# floppycontrol_mcu.net
KiCad netlist of a schematic drawn in EAGLE
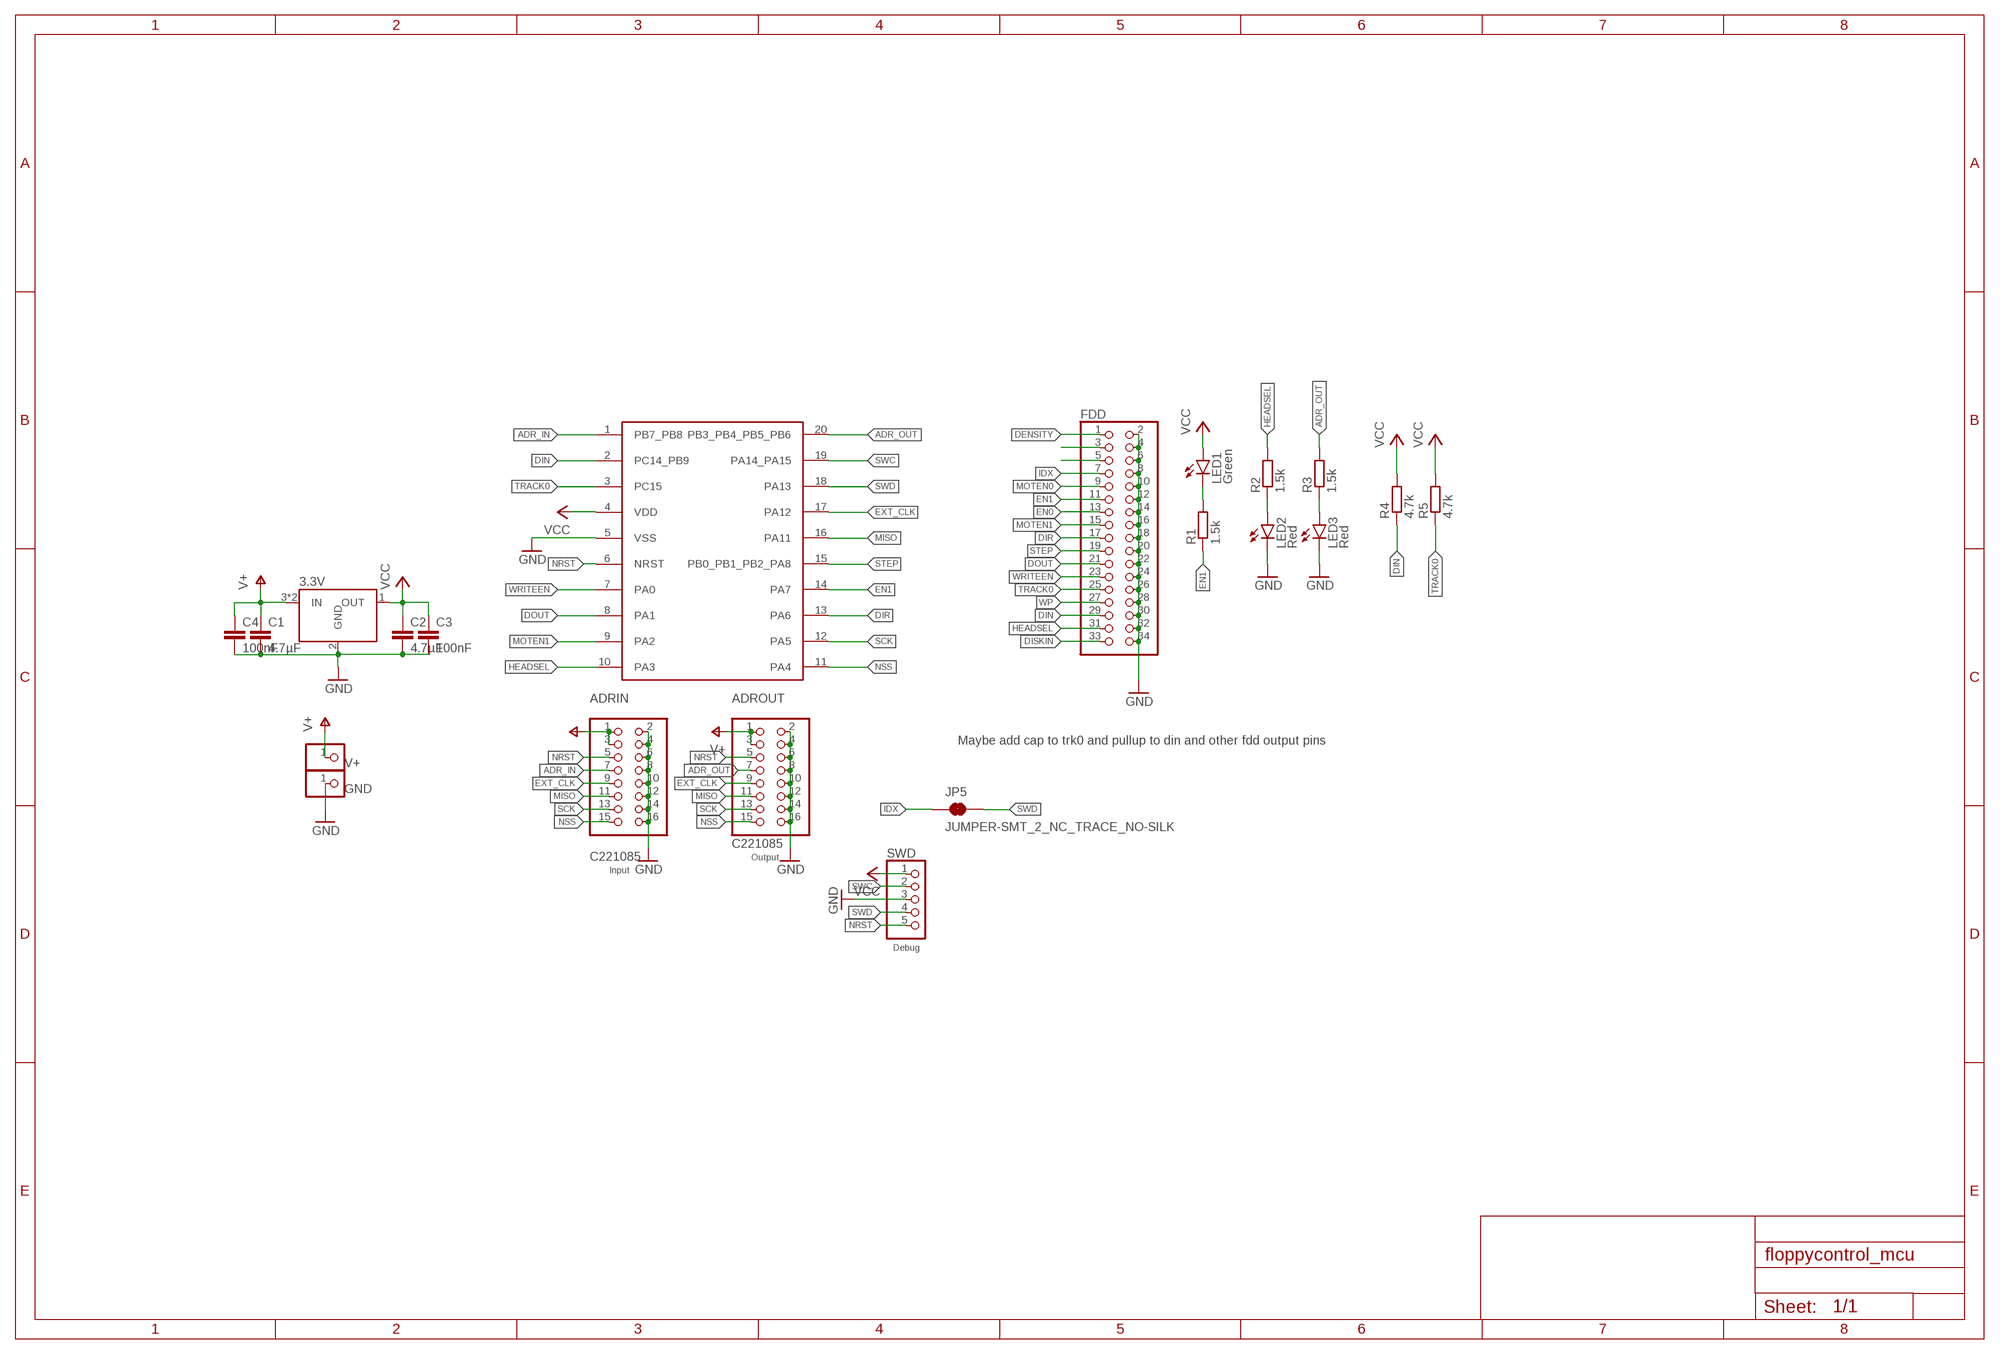
[diagram p0: schematic, sheet 1]

(export (version "E")
  (design (tool "Eeschema 10.0.6"))
  (components
    (comp (ref "ADRIN")
      (value "C221085")
      (footprint "eagle-import:2X08_90")
      (libsource (lib "eagle-import") (part "PINHD-2X8/90"))
    )
    (comp (ref "ADROUT")
      (value "C221085")
      (footprint "eagle-import:2X08_90")
      (libsource (lib "eagle-import") (part "PINHD-2X8/90"))
    )
    (comp (ref "C1")
      (value "4.7µF")
      (footprint "eagle-import:C0603")
      (libsource (lib "eagle-import") (part "C-EUC0603"))
    )
    (comp (ref "C2")
      (value "4.7µF")
      (footprint "eagle-import:C0603")
      (libsource (lib "eagle-import") (part "C-EUC0603"))
    )
    (comp (ref "C3")
      (value "100nF")
      (footprint "eagle-import:C0603")
      (libsource (lib "eagle-import") (part "C-EUC0603"))
    )
    (comp (ref "C4")
      (value "100nF")
      (footprint "eagle-import:C0603")
      (libsource (lib "eagle-import") (part "C-EUC0603"))
    )
    (comp (ref "FDD")
      (value "PINHD-2X17/90")
      (footprint "eagle-import:2X17_90")
      (libsource (lib "eagle-import") (part "PINHD-2X17/90"))
    )
    (comp (ref "GND")
      (value "PINHD-1X1")
      (footprint "eagle-import:1X01")
      (libsource (lib "eagle-import") (part "PINHD-1X1"))
    )
    (comp (ref "JP5")
      (value "JUMPER-SMT_2_NC_TRACE_NO-SILK")
      (footprint "eagle-import:SMT-JUMPER_2_NC_TRACE_NO-SILK")
      (libsource (lib "eagle-import") (part "JUMPER-SMT_2_NC_TRACE_NO-SILK"))
    )
    (comp (ref "LED1")
      (value "Green")
      (footprint "eagle-import:CHIP-LED0805")
      (libsource (lib "eagle-import") (part "LEDCHIP-LED0805"))
    )
    (comp (ref "LED2")
      (value "Red")
      (footprint "eagle-import:CHIP-LED0805")
      (libsource (lib "eagle-import") (part "LEDCHIP-LED0805"))
    )
    (comp (ref "LED3")
      (value "Red")
      (footprint "eagle-import:CHIP-LED0805")
      (libsource (lib "eagle-import") (part "LEDCHIP-LED0805"))
    )
    (comp (ref "R1")
      (value "1.5k")
      (footprint "eagle-import:R0603")
      (libsource (lib "eagle-import") (part "R-EU_R0603"))
    )
    (comp (ref "R2")
      (value "1.5k")
      (footprint "eagle-import:R0603")
      (libsource (lib "eagle-import") (part "R-EU_R0603"))
    )
    (comp (ref "R3")
      (value "1.5k")
      (footprint "eagle-import:R0603")
      (libsource (lib "eagle-import") (part "R-EU_R0603"))
    )
    (comp (ref "R4")
      (value "4.7k")
      (footprint "eagle-import:R0603")
      (libsource (lib "eagle-import") (part "R-EU_R0603"))
    )
    (comp (ref "R5")
      (value "4.7k")
      (footprint "eagle-import:R0603")
      (libsource (lib "eagle-import") (part "R-EU_R0603"))
    )
    (comp (ref "SWD")
      (value "PINHD-1X5")
      (footprint "eagle-import:1X05")
      (libsource (lib "eagle-import") (part "PINHD-1X5"))
    )
    (comp (ref "U1")
      (value "STM32G030F6P6TSSOP20")
      (footprint "eagle-import:TSSOP20")
      (libsource (lib "eagle-import") (part "STM32G030F6P6TSSOP20"))
    )
    (comp (ref "U2")
      (value "3.3V")
      (footprint "eagle-import:SOT89-R")
      (libsource (lib "eagle-import") (part "LDO_FIXEDSOT89_GND_VIN_VOUT"))
    )
    (comp (ref "V+")
      (value "PINHD-1X1")
      (footprint "eagle-import:1X01")
      (libsource (lib "eagle-import") (part "PINHD-1X1"))
    )
  )
  (nets
    (net (code "1") (name "ADR_IN") (class "Default")
      (node (ref "ADRIN") (pin "7") (pinfunction "7_7") (pintype "passive"))
      (node (ref "U1") (pin "1") (pinfunction "PB7_PB8_1") (pintype "bidirectional"))
    )
    (net (code "2") (name "ADR_OUT") (class "Default")
      (node (ref "ADROUT") (pin "7") (pinfunction "7_7") (pintype "passive"))
      (node (ref "R3") (pin "2") (pinfunction "2_2") (pintype "passive"))
      (node (ref "U1") (pin "20") (pinfunction "PB3_PB4_PB5_PB6_20") (pintype "bidirectional"))
    )
    (net (code "3") (name "DENSITY") (class "Default")
      (node (ref "FDD") (pin "1") (pinfunction "1_1") (pintype "passive"))
    )
    (net (code "4") (name "DIN") (class "Default")
      (node (ref "FDD") (pin "29") (pinfunction "29_29") (pintype "passive"))
      (node (ref "R4") (pin "1") (pinfunction "1_1") (pintype "passive"))
      (node (ref "U1") (pin "2") (pinfunction "PC14_PB9_2") (pintype "bidirectional"))
    )
    (net (code "5") (name "DIR") (class "Default")
      (node (ref "FDD") (pin "17") (pinfunction "17_17") (pintype "passive"))
      (node (ref "U1") (pin "13") (pinfunction "PA6_13") (pintype "bidirectional"))
    )
    (net (code "6") (name "DISKIN") (class "Default")
      (node (ref "FDD") (pin "33") (pinfunction "33_33") (pintype "passive"))
    )
    (net (code "7") (name "DOUT") (class "Default")
      (node (ref "FDD") (pin "21") (pinfunction "21_21") (pintype "passive"))
      (node (ref "U1") (pin "8") (pinfunction "PA1_8") (pintype "bidirectional"))
    )
    (net (code "8") (name "EN0") (class "Default")
      (node (ref "FDD") (pin "13") (pinfunction "13_13") (pintype "passive"))
    )
    (net (code "9") (name "EN1") (class "Default")
      (node (ref "FDD") (pin "11") (pinfunction "11_11") (pintype "passive"))
      (node (ref "R1") (pin "1") (pinfunction "1_1") (pintype "passive"))
      (node (ref "U1") (pin "14") (pinfunction "PA7_14") (pintype "bidirectional"))
    )
    (net (code "10") (name "EXT_CLK") (class "Default")
      (node (ref "ADRIN") (pin "9") (pinfunction "9_9") (pintype "passive"))
      (node (ref "ADROUT") (pin "9") (pinfunction "9_9") (pintype "passive"))
      (node (ref "U1") (pin "17") (pinfunction "PA12_17") (pintype "bidirectional"))
    )
    (net (code "11") (name "GND") (class "Default")
      (node (ref "ADRIN") (pin "10") (pinfunction "10_10") (pintype "passive"))
      (node (ref "ADRIN") (pin "12") (pinfunction "12_12") (pintype "passive"))
      (node (ref "ADRIN") (pin "14") (pinfunction "14_14") (pintype "passive"))
      (node (ref "ADRIN") (pin "16") (pinfunction "16_16") (pintype "passive"))
      (node (ref "ADRIN") (pin "2") (pinfunction "2_2") (pintype "passive"))
      (node (ref "ADRIN") (pin "4") (pinfunction "4_4") (pintype "passive"))
      (node (ref "ADRIN") (pin "6") (pinfunction "6_6") (pintype "passive"))
      (node (ref "ADRIN") (pin "8") (pinfunction "8_8") (pintype "passive"))
      (node (ref "ADROUT") (pin "10") (pinfunction "10_10") (pintype "passive"))
      (node (ref "ADROUT") (pin "12") (pinfunction "12_12") (pintype "passive"))
      (node (ref "ADROUT") (pin "14") (pinfunction "14_14") (pintype "passive"))
      (node (ref "ADROUT") (pin "16") (pinfunction "16_16") (pintype "passive"))
      (node (ref "ADROUT") (pin "2") (pinfunction "2_2") (pintype "passive"))
      (node (ref "ADROUT") (pin "4") (pinfunction "4_4") (pintype "passive"))
      (node (ref "ADROUT") (pin "6") (pinfunction "6_6") (pintype "passive"))
      (node (ref "ADROUT") (pin "8") (pinfunction "8_8") (pintype "passive"))
      (node (ref "C1") (pin "2") (pinfunction "2_2") (pintype "passive"))
      (node (ref "C2") (pin "2") (pinfunction "2_2") (pintype "passive"))
      (node (ref "C3") (pin "2") (pinfunction "2_2") (pintype "passive"))
      (node (ref "C4") (pin "2") (pinfunction "2_2") (pintype "passive"))
      (node (ref "FDD") (pin "10") (pinfunction "10_10") (pintype "passive"))
      (node (ref "FDD") (pin "12") (pinfunction "12_12") (pintype "passive"))
      (node (ref "FDD") (pin "14") (pinfunction "14_14") (pintype "passive"))
      (node (ref "FDD") (pin "16") (pinfunction "16_16") (pintype "passive"))
      (node (ref "FDD") (pin "18") (pinfunction "18_18") (pintype "passive"))
      (node (ref "FDD") (pin "2") (pinfunction "2_2") (pintype "passive"))
      (node (ref "FDD") (pin "20") (pinfunction "20_20") (pintype "passive"))
      (node (ref "FDD") (pin "22") (pinfunction "22_22") (pintype "passive"))
      (node (ref "FDD") (pin "24") (pinfunction "24_24") (pintype "passive"))
      (node (ref "FDD") (pin "26") (pinfunction "26_26") (pintype "passive"))
      (node (ref "FDD") (pin "28") (pinfunction "28_28") (pintype "passive"))
      (node (ref "FDD") (pin "30") (pinfunction "30_30") (pintype "passive"))
      (node (ref "FDD") (pin "32") (pinfunction "32_32") (pintype "passive"))
      (node (ref "FDD") (pin "34") (pinfunction "34_34") (pintype "passive"))
      (node (ref "FDD") (pin "4") (pinfunction "4_4") (pintype "passive"))
      (node (ref "FDD") (pin "6") (pinfunction "6_6") (pintype "passive"))
      (node (ref "FDD") (pin "8") (pinfunction "8_8") (pintype "passive"))
      (node (ref "GND") (pin "1") (pinfunction "1_1") (pintype "passive"))
      (node (ref "LED2") (pin "C") (pinfunction "C_C") (pintype "passive"))
      (node (ref "LED3") (pin "C") (pinfunction "C_C") (pintype "passive"))
      (node (ref "SWD") (pin "3") (pinfunction "3_3") (pintype "passive"))
      (node (ref "U1") (pin "5") (pinfunction "VSS_5") (pintype "bidirectional"))
      (node (ref "U2") (pin "2") (pinfunction "GND_2") (pintype "power_in"))
    )
    (net (code "12") (name "HEADSEL") (class "Default")
      (node (ref "FDD") (pin "31") (pinfunction "31_31") (pintype "passive"))
      (node (ref "R2") (pin "2") (pinfunction "2_2") (pintype "passive"))
      (node (ref "U1") (pin "10") (pinfunction "PA3_10") (pintype "bidirectional"))
    )
    (net (code "13") (name "IDX") (class "Default")
      (node (ref "FDD") (pin "7") (pinfunction "7_7") (pintype "passive"))
      (node (ref "JP5") (pin "1") (pinfunction "1_1") (pintype "passive"))
    )
    (net (code "14") (name "MISO") (class "Default")
      (node (ref "ADRIN") (pin "11") (pinfunction "11_11") (pintype "passive"))
      (node (ref "ADROUT") (pin "11") (pinfunction "11_11") (pintype "passive"))
      (node (ref "U1") (pin "16") (pinfunction "PA11_16") (pintype "bidirectional"))
    )
    (net (code "15") (name "MOTEN0") (class "Default")
      (node (ref "FDD") (pin "9") (pinfunction "9_9") (pintype "passive"))
    )
    (net (code "16") (name "MOTEN1") (class "Default")
      (node (ref "FDD") (pin "15") (pinfunction "15_15") (pintype "passive"))
      (node (ref "U1") (pin "9") (pinfunction "PA2_9") (pintype "bidirectional"))
    )
    (net (code "17") (name "NRST") (class "Default")
      (node (ref "ADRIN") (pin "5") (pinfunction "5_5") (pintype "passive"))
      (node (ref "ADROUT") (pin "5") (pinfunction "5_5") (pintype "passive"))
      (node (ref "SWD") (pin "5") (pinfunction "5_5") (pintype "passive"))
      (node (ref "U1") (pin "6") (pinfunction "NRST_6") (pintype "bidirectional"))
    )
    (net (code "18") (name "NSS") (class "Default")
      (node (ref "ADRIN") (pin "15") (pinfunction "15_15") (pintype "passive"))
      (node (ref "ADROUT") (pin "15") (pinfunction "15_15") (pintype "passive"))
      (node (ref "U1") (pin "11") (pinfunction "PA4_11") (pintype "bidirectional"))
    )
    (net (code "19") (name "Net-(LED1-PadC)") (class "Default")
      (node (ref "LED1") (pin "C") (pinfunction "C_C") (pintype "passive"))
      (node (ref "R1") (pin "2") (pinfunction "2_2") (pintype "passive"))
    )
    (net (code "20") (name "Net-(LED2-PadA)") (class "Default")
      (node (ref "LED2") (pin "A") (pinfunction "A_A") (pintype "passive"))
      (node (ref "R2") (pin "1") (pinfunction "1_1") (pintype "passive"))
    )
    (net (code "21") (name "Net-(LED3-PadA)") (class "Default")
      (node (ref "LED3") (pin "A") (pinfunction "A_A") (pintype "passive"))
      (node (ref "R3") (pin "1") (pinfunction "1_1") (pintype "passive"))
    )
    (net (code "22") (name "SCK") (class "Default")
      (node (ref "ADRIN") (pin "13") (pinfunction "13_13") (pintype "passive"))
      (node (ref "ADROUT") (pin "13") (pinfunction "13_13") (pintype "passive"))
      (node (ref "U1") (pin "12") (pinfunction "PA5_12") (pintype "bidirectional"))
    )
    (net (code "23") (name "STEP") (class "Default")
      (node (ref "FDD") (pin "19") (pinfunction "19_19") (pintype "passive"))
      (node (ref "U1") (pin "15") (pinfunction "PB0_PB1_PB2_PA8_15") (pintype "bidirectional"))
    )
    (net (code "24") (name "SWC") (class "Default")
      (node (ref "SWD") (pin "2") (pinfunction "2_2") (pintype "passive"))
      (node (ref "U1") (pin "19") (pinfunction "PA14_PA15_19") (pintype "bidirectional"))
    )
    (net (code "25") (name "SWD") (class "Default")
      (node (ref "JP5") (pin "2") (pinfunction "2_2") (pintype "passive"))
      (node (ref "SWD") (pin "4") (pinfunction "4_4") (pintype "passive"))
      (node (ref "U1") (pin "18") (pinfunction "PA13_18") (pintype "bidirectional"))
    )
    (net (code "26") (name "TRACK0") (class "Default")
      (node (ref "FDD") (pin "25") (pinfunction "25_25") (pintype "passive"))
      (node (ref "R5") (pin "1") (pinfunction "1_1") (pintype "passive"))
      (node (ref "U1") (pin "3") (pinfunction "PC15_3") (pintype "bidirectional"))
    )
    (net (code "27") (name "V+") (class "Default")
      (node (ref "ADRIN") (pin "1") (pinfunction "1_1") (pintype "passive"))
      (node (ref "ADRIN") (pin "3") (pinfunction "3_3") (pintype "passive"))
      (node (ref "ADROUT") (pin "1") (pinfunction "1_1") (pintype "passive"))
      (node (ref "ADROUT") (pin "3") (pinfunction "3_3") (pintype "passive"))
      (node (ref "C1") (pin "1") (pinfunction "1_1") (pintype "passive"))
      (node (ref "C4") (pin "1") (pinfunction "1_1") (pintype "passive"))
      (node (ref "U2") (pin "3") (pinfunction "IN_3") (pintype "bidirectional"))
      (node (ref "U2") (pin "4") (pinfunction "IN_4") (pintype "bidirectional"))
      (node (ref "V+") (pin "1") (pinfunction "1_1") (pintype "passive"))
    )
    (net (code "28") (name "VCC") (class "Default")
      (node (ref "C2") (pin "1") (pinfunction "1_1") (pintype "passive"))
      (node (ref "C3") (pin "1") (pinfunction "1_1") (pintype "passive"))
      (node (ref "LED1") (pin "A") (pinfunction "A_A") (pintype "passive"))
      (node (ref "R4") (pin "2") (pinfunction "2_2") (pintype "passive"))
      (node (ref "R5") (pin "2") (pinfunction "2_2") (pintype "passive"))
      (node (ref "SWD") (pin "1") (pinfunction "1_1") (pintype "passive"))
      (node (ref "U1") (pin "4") (pinfunction "VDD_4") (pintype "bidirectional"))
      (node (ref "U2") (pin "1") (pinfunction "OUT_1") (pintype "bidirectional"))
    )
    (net (code "29") (name "WP") (class "Default")
      (node (ref "FDD") (pin "27") (pinfunction "27_27") (pintype "passive"))
    )
    (net (code "30") (name "WRITEEN") (class "Default")
      (node (ref "FDD") (pin "23") (pinfunction "23_23") (pintype "passive"))
      (node (ref "U1") (pin "7") (pinfunction "PA0_7") (pintype "bidirectional"))
    )
    (net (code "31") (name "unconnected-(FDD-Pad3)") (class "Default")
      (node (ref "FDD") (pin "3") (pinfunction "3_3") (pintype "passive"))
    )
    (net (code "32") (name "unconnected-(FDD-Pad5)") (class "Default")
      (node (ref "FDD") (pin "5") (pinfunction "5_5") (pintype "passive"))
    )
  )
)
